# esp-12.net
KiCad netlist of a schematic drawn in EAGLE
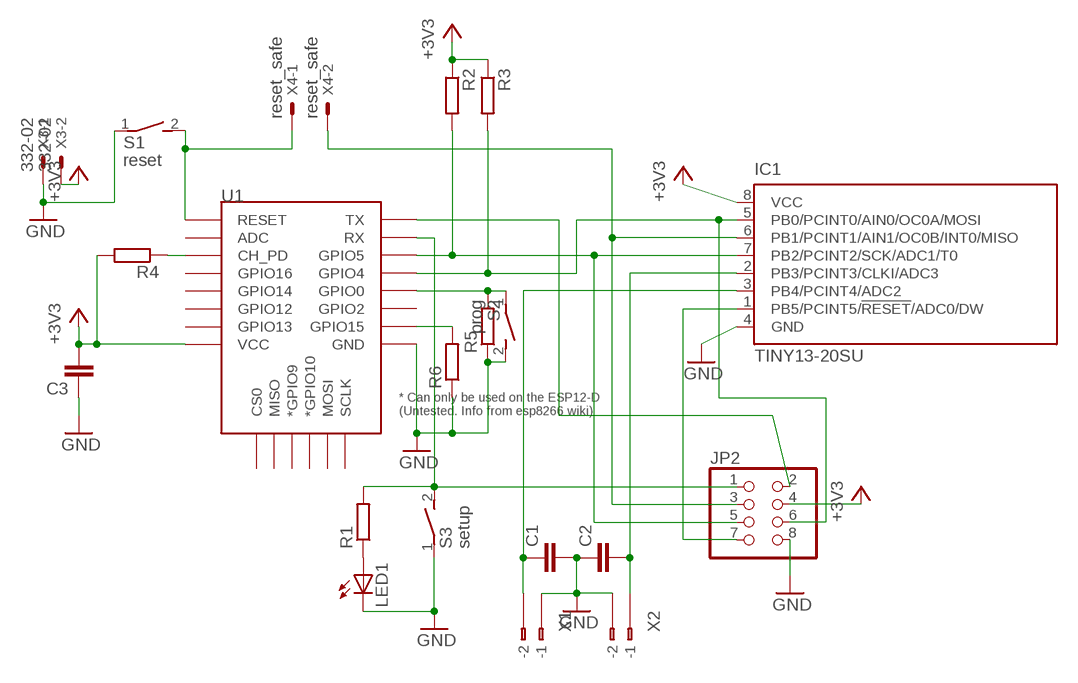
[diagram p0: schematic, sheet 1]

(export (version "E")
  (design (tool "Eeschema 10.0.6"))
  (components
    (comp (ref "C1")
      (value "C-EUC0805")
      (footprint "eagle-import:C0805")
      (libsource (lib "eagle-import") (part "C-EUC0805"))
    )
    (comp (ref "C2")
      (value "C-EUC0805")
      (footprint "eagle-import:C0805")
      (libsource (lib "eagle-import") (part "C-EUC0805"))
    )
    (comp (ref "C3")
      (value "C-EUC0805")
      (footprint "eagle-import:C0805")
      (libsource (lib "eagle-import") (part "C-EUC0805"))
    )
    (comp (ref "IC1")
      (value "TINY13-20SU")
      (footprint "eagle-import:8S2")
      (fields (field (name "MPN") "ATTINY13-20SU"))
      (libsource (lib "eagle-import") (part "TINY13SU-20"))
    )
    (comp (ref "JP2")
      (value "PINHD-2X4")
      (footprint "eagle-import:2X04")
      (libsource (lib "eagle-import") (part "PINHD-2X4"))
    )
    (comp (ref "LED1")
      (value "LEDSQR2X5")
      (footprint "eagle-import:LED2X5")
      (libsource (lib "eagle-import") (part "LEDSQR2X5"))
    )
    (comp (ref "R1")
      (value "R-EU_R0805")
      (footprint "eagle-import:R0805")
      (libsource (lib "eagle-import") (part "R-EU_R0805"))
    )
    (comp (ref "R2")
      (value "R-EU_R0805")
      (footprint "eagle-import:R0805")
      (libsource (lib "eagle-import") (part "R-EU_R0805"))
    )
    (comp (ref "R3")
      (value "R-EU_R0805")
      (footprint "eagle-import:R0805")
      (libsource (lib "eagle-import") (part "R-EU_R0805"))
    )
    (comp (ref "R4")
      (value "R-EU_R0805")
      (footprint "eagle-import:R0805")
      (libsource (lib "eagle-import") (part "R-EU_R0805"))
    )
    (comp (ref "R5")
      (value "R-EU_R0805")
      (footprint "eagle-import:R0805")
      (libsource (lib "eagle-import") (part "R-EU_R0805"))
    )
    (comp (ref "R6")
      (value "R-EU_R0805")
      (footprint "eagle-import:R0805")
      (libsource (lib "eagle-import") (part "R-EU_R0805"))
    )
    (comp (ref "S1")
      (value "reset")
      (footprint "eagle-import:DS-01")
      (libsource (lib "eagle-import") (part "DS01E"))
    )
    (comp (ref "S2")
      (value "prog")
      (footprint "eagle-import:DS-01")
      (libsource (lib "eagle-import") (part "DS01E"))
    )
    (comp (ref "S3")
      (value "setup")
      (footprint "eagle-import:DS-01")
      (libsource (lib "eagle-import") (part "DS01E"))
    )
    (comp (ref "U1")
      (value "ESP12ESMD")
      (footprint "eagle-import:ESP12E-SMD")
      (libsource (lib "eagle-import") (part "ESP12ESMD"))
    )
    (comp (ref "X1")
      (value "233-102")
      (footprint "eagle-import:233-102")
      (libsource (lib "eagle-import") (part "233-102"))
    )
    (comp (ref "X2")
      (value "233-102")
      (footprint "eagle-import:233-102")
      (libsource (lib "eagle-import") (part "233-102"))
    )
    (comp (ref "X3")
      (value "332-02")
      (footprint "eagle-import:332-02")
      (libsource (lib "eagle-import") (part "332-02"))
    )
    (comp (ref "X4")
      (value "reset_safe")
      (footprint "eagle-import:332-02")
      (libsource (lib "eagle-import") (part "332-02"))
    )
  )
  (nets
    (net (code "1") (name "+3V3") (class "Default")
      (node (ref "C3") (pin "2") (pinfunction "2_2") (pintype "passive"))
      (node (ref "IC1") (pin "8") (pinfunction "VCC_8") (pintype "power_in"))
      (node (ref "JP2") (pin "4") (pinfunction "4_4") (pintype "passive"))
      (node (ref "R2") (pin "1") (pinfunction "1_1") (pintype "passive"))
      (node (ref "R3") (pin "1") (pinfunction "1_1") (pintype "passive"))
      (node (ref "R4") (pin "2") (pinfunction "2_2") (pintype "passive"))
      (node (ref "U1") (pin "VCC") (pinfunction "VCC_VCC") (pintype "bidirectional"))
      (node (ref "X3") (pin "2") (pinfunction "S_2") (pintype "passive"))
    )
    (net (code "2") (name "GND") (class "Default")
      (node (ref "C1") (pin "2") (pinfunction "2_2") (pintype "passive"))
      (node (ref "C2") (pin "1") (pinfunction "1_1") (pintype "passive"))
      (node (ref "C3") (pin "1") (pinfunction "1_1") (pintype "passive"))
      (node (ref "IC1") (pin "4") (pinfunction "GND_4") (pintype "power_in"))
      (node (ref "JP2") (pin "8") (pinfunction "8_8") (pintype "passive"))
      (node (ref "LED1") (pin "K") (pinfunction "C_K") (pintype "passive"))
      (node (ref "R5") (pin "1") (pinfunction "1_1") (pintype "passive"))
      (node (ref "R6") (pin "1") (pinfunction "1_1") (pintype "passive"))
      (node (ref "S1") (pin "1") (pinfunction "1_1") (pintype "passive"))
      (node (ref "S2") (pin "2") (pinfunction "2_2") (pintype "passive"))
      (node (ref "S3") (pin "1") (pinfunction "1_1") (pintype "passive"))
      (node (ref "U1") (pin "GND") (pinfunction "GND_GND") (pintype "bidirectional"))
      (node (ref "X1") (pin "B1") (pinfunction "B-1_B1") (pintype "passive"))
      (node (ref "X2") (pin "B2") (pinfunction "B-2_B2") (pintype "passive"))
      (node (ref "X3") (pin "1") (pinfunction "S_1") (pintype "passive"))
    )
    (net (code "3") (name "Net-(IC1-PB0{slash}PCINT0{slash}AIN0{slash}OC0A{slash}MOSI)") (class "Default")
      (node (ref "IC1") (pin "5") (pinfunction "PB0/PCINT0/AIN0/OC0A/MOSI_5") (pintype "bidirectional"))
      (node (ref "JP2") (pin "6") (pinfunction "6_6") (pintype "passive"))
      (node (ref "R3") (pin "2") (pinfunction "2_2") (pintype "passive"))
      (node (ref "U1") (pin "GPIO4") (pinfunction "GPIO4_GPIO4") (pintype "bidirectional"))
    )
    (net (code "4") (name "Net-(IC1-PB1{slash}PCINT1{slash}AIN1{slash}OC0B{slash}INT0{slash}MISO)") (class "Default")
      (node (ref "IC1") (pin "6") (pinfunction "PB1/PCINT1/AIN1/OC0B/INT0/MISO_6") (pintype "bidirectional"))
      (node (ref "JP2") (pin "3") (pinfunction "3_3") (pintype "passive"))
      (node (ref "X4") (pin "2") (pinfunction "S_2") (pintype "passive"))
    )
    (net (code "5") (name "Net-(IC1-PB2{slash}PCINT2{slash}SCK{slash}ADC1{slash}T0)") (class "Default")
      (node (ref "IC1") (pin "7") (pinfunction "PB2/PCINT2/SCK/ADC1/T0_7") (pintype "bidirectional"))
      (node (ref "JP2") (pin "5") (pinfunction "5_5") (pintype "passive"))
      (node (ref "R2") (pin "2") (pinfunction "2_2") (pintype "passive"))
      (node (ref "U1") (pin "GPIO5") (pinfunction "GPIO5_GPIO5") (pintype "bidirectional"))
    )
    (net (code "6") (name "Net-(IC1-PB3{slash}PCINT3{slash}CLKI{slash}ADC3)") (class "Default")
      (node (ref "C2") (pin "2") (pinfunction "2_2") (pintype "passive"))
      (node (ref "IC1") (pin "2") (pinfunction "PB3/PCINT3/CLKI/ADC3_2") (pintype "bidirectional"))
      (node (ref "X2") (pin "B1") (pinfunction "B-1_B1") (pintype "passive"))
    )
    (net (code "7") (name "Net-(IC1-PB4{slash}PCINT4{slash}ADC2)") (class "Default")
      (node (ref "C1") (pin "1") (pinfunction "1_1") (pintype "passive"))
      (node (ref "IC1") (pin "3") (pinfunction "PB4/PCINT4/ADC2_3") (pintype "bidirectional"))
      (node (ref "X1") (pin "B2") (pinfunction "B-2_B2") (pintype "passive"))
    )
    (net (code "8") (name "Net-(IC1-PB5{slash}PCINT5{slash}~{RESET}{slash}ADC0{slash}DW)") (class "Default")
      (node (ref "IC1") (pin "1") (pinfunction "PB5/PCINT5/~{RESET}/ADC0/DW_1") (pintype "bidirectional"))
      (node (ref "JP2") (pin "7") (pinfunction "7_7") (pintype "passive"))
    )
    (net (code "9") (name "Net-(LED1-PadA)") (class "Default")
      (node (ref "LED1") (pin "A") (pinfunction "A_A") (pintype "passive"))
      (node (ref "R1") (pin "1") (pinfunction "1_1") (pintype "passive"))
    )
    (net (code "10") (name "Net-(R4-Pad1)") (class "Default")
      (node (ref "R4") (pin "1") (pinfunction "1_1") (pintype "passive"))
      (node (ref "U1") (pin "CH_PD") (pinfunction "CH_PD_CH_PD") (pintype "bidirectional"))
    )
    (net (code "11") (name "Net-(R5-Pad2)") (class "Default")
      (node (ref "R5") (pin "2") (pinfunction "2_2") (pintype "passive"))
      (node (ref "S2") (pin "1") (pinfunction "1_1") (pintype "passive"))
      (node (ref "U1") (pin "GPIO0") (pinfunction "GPIO0_GPIO0") (pintype "bidirectional"))
    )
    (net (code "12") (name "Net-(R6-Pad2)") (class "Default")
      (node (ref "R6") (pin "2") (pinfunction "2_2") (pintype "passive"))
      (node (ref "U1") (pin "GPIO15") (pinfunction "GPIO15_GPIO15") (pintype "bidirectional"))
    )
    (net (code "13") (name "Net-(U1-RX)") (class "Default")
      (node (ref "JP2") (pin "1") (pinfunction "1_1") (pintype "passive"))
      (node (ref "R1") (pin "2") (pinfunction "2_2") (pintype "passive"))
      (node (ref "S3") (pin "2") (pinfunction "2_2") (pintype "passive"))
      (node (ref "U1") (pin "RXD0") (pinfunction "RX_RXD0") (pintype "bidirectional"))
    )
    (net (code "14") (name "Net-(U1-TX)") (class "Default")
      (node (ref "JP2") (pin "2") (pinfunction "2_2") (pintype "passive"))
      (node (ref "U1") (pin "TXD0") (pinfunction "TX_TXD0") (pintype "bidirectional"))
    )
    (net (code "15") (name "Net-(X4A-S)") (class "Default")
      (node (ref "S1") (pin "2") (pinfunction "2_2") (pintype "passive"))
      (node (ref "U1") (pin "RESET") (pinfunction "RESET_RESET") (pintype "bidirectional"))
      (node (ref "X4") (pin "1") (pinfunction "S_1") (pintype "passive"))
    )
    (net (code "16") (name "unconnected-(U1-*GPIO9-PadGPIO9)") (class "Default")
      (node (ref "U1") (pin "GPIO9") (pinfunction "*GPIO9_GPIO9") (pintype "bidirectional"))
    )
    (net (code "17") (name "unconnected-(U1-*GPIO10-PadGPIO10)") (class "Default")
      (node (ref "U1") (pin "GPIO10") (pinfunction "*GPIO10_GPIO10") (pintype "bidirectional"))
    )
    (net (code "18") (name "unconnected-(U1-PadADC)") (class "Default")
      (node (ref "U1") (pin "ADC") (pinfunction "ADC_ADC") (pintype "bidirectional"))
    )
    (net (code "19") (name "unconnected-(U1-PadCS0)") (class "Default")
      (node (ref "U1") (pin "CS0") (pinfunction "CS0_CS0") (pintype "bidirectional"))
    )
    (net (code "20") (name "unconnected-(U1-PadGPIO2)") (class "Default")
      (node (ref "U1") (pin "GPIO2") (pinfunction "GPIO2_GPIO2") (pintype "bidirectional"))
    )
    (net (code "21") (name "unconnected-(U1-PadGPIO12)") (class "Default")
      (node (ref "U1") (pin "GPIO12") (pinfunction "GPIO12_GPIO12") (pintype "bidirectional"))
    )
    (net (code "22") (name "unconnected-(U1-PadGPIO13)") (class "Default")
      (node (ref "U1") (pin "GPIO13") (pinfunction "GPIO13_GPIO13") (pintype "bidirectional"))
    )
    (net (code "23") (name "unconnected-(U1-PadGPIO14)") (class "Default")
      (node (ref "U1") (pin "GPIO14") (pinfunction "GPIO14_GPIO14") (pintype "bidirectional"))
    )
    (net (code "24") (name "unconnected-(U1-PadGPIO16)") (class "Default")
      (node (ref "U1") (pin "GPIO16") (pinfunction "GPIO16_GPIO16") (pintype "bidirectional"))
    )
    (net (code "25") (name "unconnected-(U1-PadMISO)") (class "Default")
      (node (ref "U1") (pin "MISO") (pinfunction "MISO_MISO") (pintype "bidirectional"))
    )
    (net (code "26") (name "unconnected-(U1-PadMOSI)") (class "Default")
      (node (ref "U1") (pin "MOSI") (pinfunction "MOSI_MOSI") (pintype "bidirectional"))
    )
    (net (code "27") (name "unconnected-(U1-PadSCLK)") (class "Default")
      (node (ref "U1") (pin "SCLK") (pinfunction "SCLK_SCLK") (pintype "bidirectional"))
    )
    (net (code "28") (name "unconnected-(X1--1-PadA1)") (class "Default")
      (node (ref "X1") (pin "A1") (pinfunction "-1_A1") (pintype "passive"))
    )
    (net (code "29") (name "unconnected-(X1--2-PadA2)") (class "Default")
      (node (ref "X1") (pin "A2") (pinfunction "-2_A2") (pintype "passive"))
    )
    (net (code "30") (name "unconnected-(X2--1-PadA1)") (class "Default")
      (node (ref "X2") (pin "A1") (pinfunction "-1_A1") (pintype "passive"))
    )
    (net (code "31") (name "unconnected-(X2--2-PadA2)") (class "Default")
      (node (ref "X2") (pin "A2") (pinfunction "-2_A2") (pintype "passive"))
    )
  )
)
